# Encoder_y_alarmas.net
KiCad netlist of a schematic drawn in EAGLE
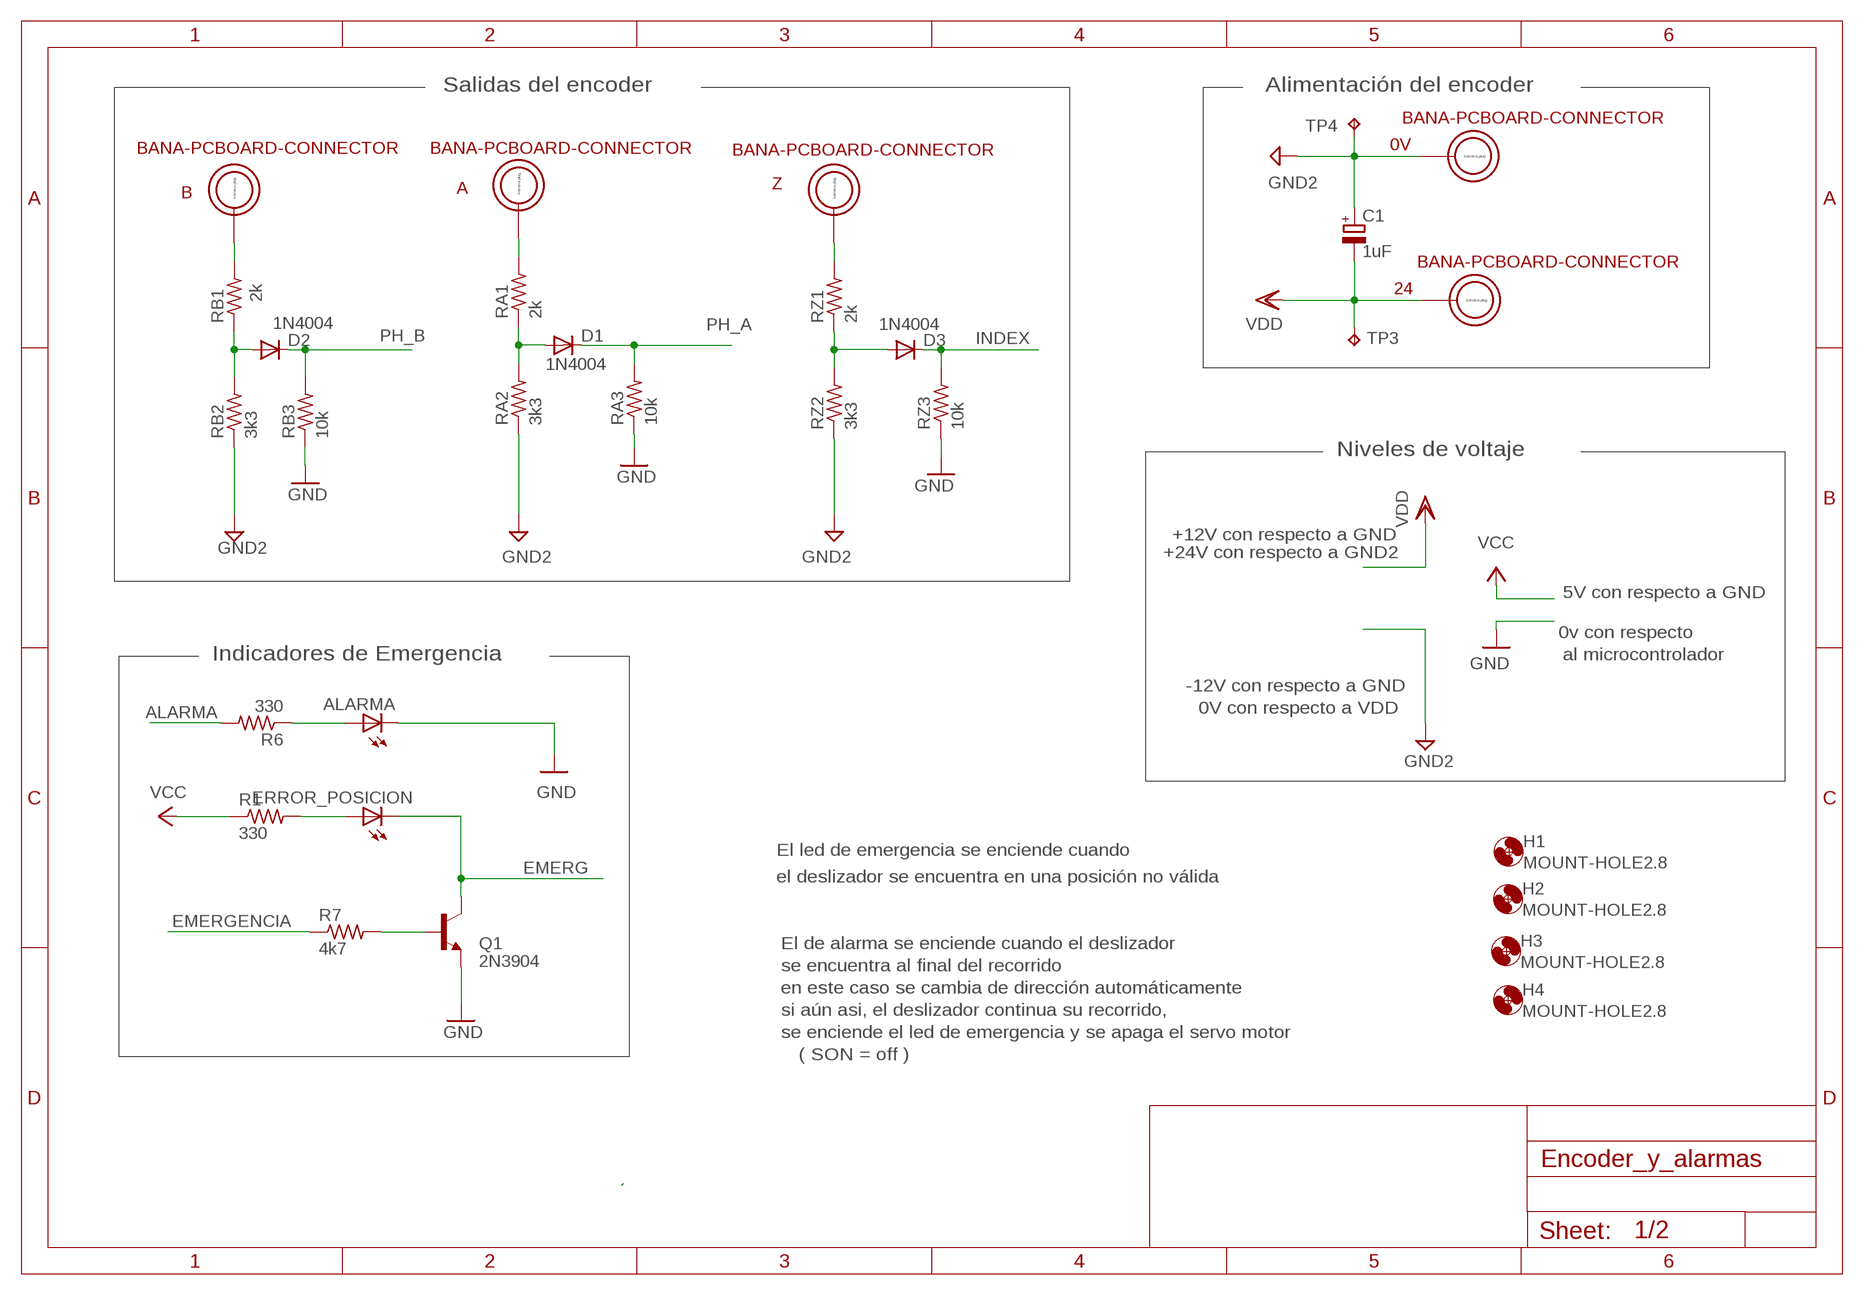
[diagram p0: schematic, sheet 1]
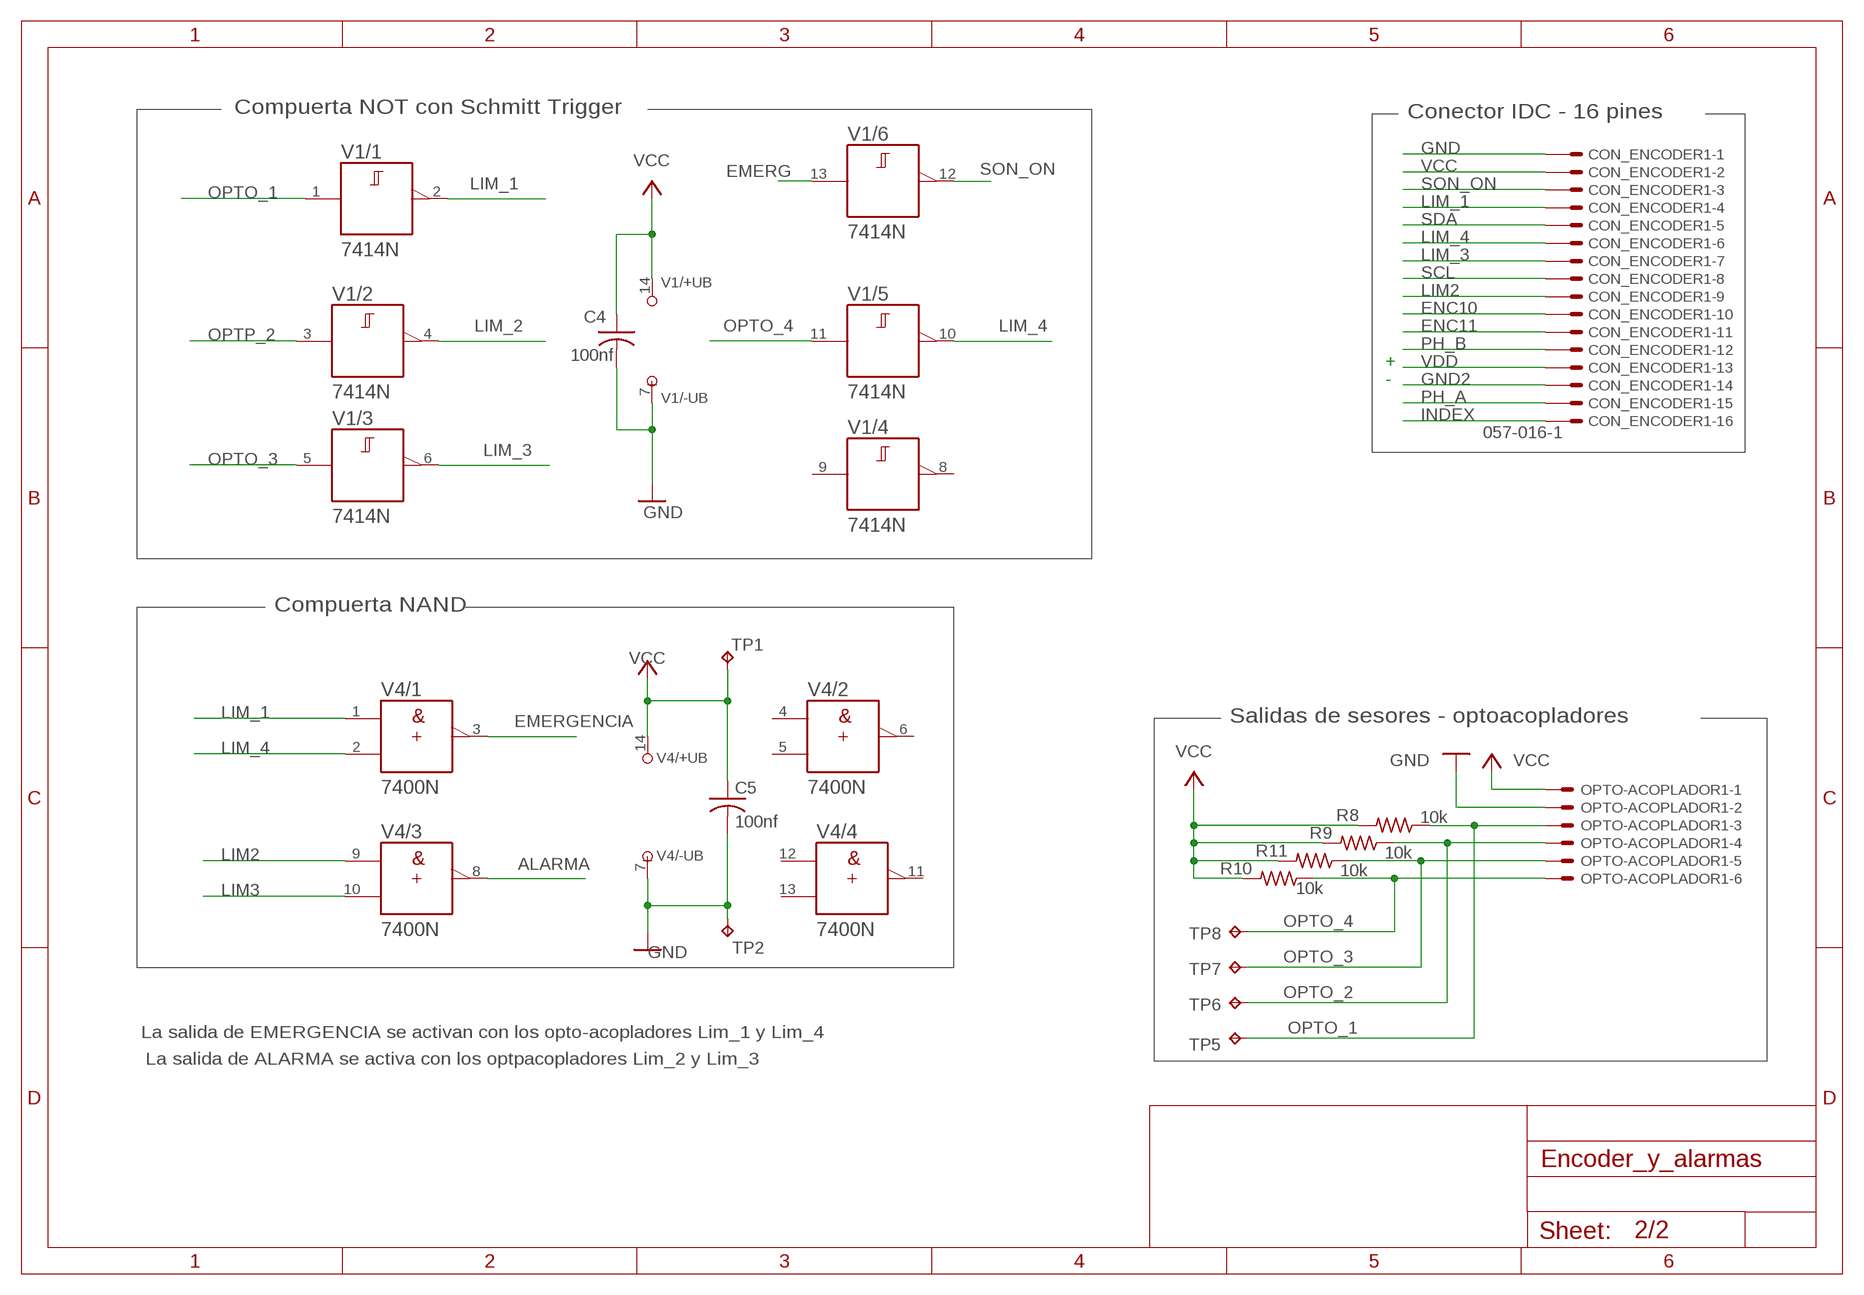
[diagram p1: schematic, sheet 2]

(export (version "E")
  (design (tool "Eeschema 10.0.6"))
  (components
    (comp (ref "C4")
      (value "100nf")
      (footprint "eagle-import:C025-024X044")
      (libsource (lib "eagle-import") (part "C-US025-024X044"))
    )
    (comp (ref "C5")
      (value "100nf")
      (footprint "eagle-import:C025-024X044")
      (libsource (lib "eagle-import") (part "C-US025-024X044"))
    )
    (comp (ref "CON_ENCODER1")
      (value "057-016-1")
      (footprint "eagle-import:057-016-1")
      (libsource (lib "eagle-import") (part "057-016-1"))
    )
    (comp (ref "OPTO-ACOPLADOR1")
      (value "22-23-2061")
      (footprint "eagle-import:22-23-2061")
      (fields (field (name "MF") "MOLEX"))
      (libsource (lib "eagle-import") (part "22-23-2061"))
    )
    (comp (ref "R8")
      (value "10k")
      (footprint "eagle-import:0204_7")
      (libsource (lib "eagle-import") (part "R-US_0204/7"))
    )
    (comp (ref "R9")
      (value "10k")
      (footprint "eagle-import:0204_7")
      (libsource (lib "eagle-import") (part "R-US_0204/7"))
    )
    (comp (ref "R10")
      (value "10k")
      (footprint "eagle-import:0204_7")
      (libsource (lib "eagle-import") (part "R-US_0204/7"))
    )
    (comp (ref "R11")
      (value "10k")
      (footprint "eagle-import:0204_7")
      (libsource (lib "eagle-import") (part "R-US_0204/7"))
    )
    (comp (ref "TP1")
      (value "TPB2,54")
      (footprint "eagle-import:B2,54")
      (libsource (lib "eagle-import") (part "TPB2,54"))
    )
    (comp (ref "TP2")
      (value "TPB2,54")
      (footprint "eagle-import:B2,54")
      (libsource (lib "eagle-import") (part "TPB2,54"))
    )
    (comp (ref "TP5")
      (value "TPB2,54")
      (footprint "eagle-import:B2,54")
      (libsource (lib "eagle-import") (part "TPB2,54"))
    )
    (comp (ref "TP6")
      (value "TPB2,54")
      (footprint "eagle-import:B2,54")
      (libsource (lib "eagle-import") (part "TPB2,54"))
    )
    (comp (ref "TP7")
      (value "TPB2,54")
      (footprint "eagle-import:B2,54")
      (libsource (lib "eagle-import") (part "TPB2,54"))
    )
    (comp (ref "TP8")
      (value "TPB2,54")
      (footprint "eagle-import:B2,54")
      (libsource (lib "eagle-import") (part "TPB2,54"))
    )
    (comp (ref "V1")
      (value "7414N")
      (footprint "eagle-import:DIL14")
      (libsource (lib "eagle-import") (part "7414N"))
    )
    (comp (ref "V4")
      (value "7400N")
      (footprint "eagle-import:DIL14")
      (libsource (lib "eagle-import") (part "7400N"))
    )
    (comp (ref "0V")
      (value "BANA-PCBOARD-CONNECTOR")
      (footprint "eagle-import:BANA_PLUG")
      (libsource (lib "eagle-import") (part "BANA-PCBOARD-CONNECTOR"))
    )
    (comp (ref "24")
      (value "BANA-PCBOARD-CONNECTOR")
      (footprint "eagle-import:BANA_PLUG")
      (libsource (lib "eagle-import") (part "BANA-PCBOARD-CONNECTOR"))
    )
    (comp (ref "A")
      (value "BANA-PCBOARD-CONNECTOR")
      (footprint "eagle-import:BANA_PLUG")
      (libsource (lib "eagle-import") (part "BANA-PCBOARD-CONNECTOR"))
    )
    (comp (ref "ALARMA")
      (value "LED5MM")
      (footprint "eagle-import:LED5MM")
      (libsource (lib "eagle-import") (part "LED5MM"))
    )
    (comp (ref "B")
      (value "BANA-PCBOARD-CONNECTOR")
      (footprint "eagle-import:BANA_PLUG")
      (libsource (lib "eagle-import") (part "BANA-PCBOARD-CONNECTOR"))
    )
    (comp (ref "C1")
      (value "1uF")
      (footprint "eagle-import:E2,5-6")
      (libsource (lib "eagle-import") (part "CPOL-EUE2.5-6"))
    )
    (comp (ref "D1")
      (value "1N4004")
      (footprint "eagle-import:DO41-10")
      (libsource (lib "eagle-import") (part "1N4004"))
    )
    (comp (ref "D2")
      (value "1N4004")
      (footprint "eagle-import:DO41-10")
      (libsource (lib "eagle-import") (part "1N4004"))
    )
    (comp (ref "D3")
      (value "1N4004")
      (footprint "eagle-import:DO41-10")
      (libsource (lib "eagle-import") (part "1N4004"))
    )
    (comp (ref "ERROR_POSICION")
      (value "LED5MM")
      (footprint "eagle-import:LED5MM")
      (libsource (lib "eagle-import") (part "LED5MM"))
    )
    (comp (ref "H1")
      (value "MOUNT-HOLE2.8")
      (footprint "eagle-import:2,8")
      (libsource (lib "eagle-import") (part "MOUNT-HOLE2.8"))
    )
    (comp (ref "H2")
      (value "MOUNT-HOLE2.8")
      (footprint "eagle-import:2,8")
      (libsource (lib "eagle-import") (part "MOUNT-HOLE2.8"))
    )
    (comp (ref "H3")
      (value "MOUNT-HOLE2.8")
      (footprint "eagle-import:2,8")
      (libsource (lib "eagle-import") (part "MOUNT-HOLE2.8"))
    )
    (comp (ref "H4")
      (value "MOUNT-HOLE2.8")
      (footprint "eagle-import:2,8")
      (libsource (lib "eagle-import") (part "MOUNT-HOLE2.8"))
    )
    (comp (ref "Q1")
      (value "2N3904")
      (footprint "eagle-import:TO92")
      (libsource (lib "eagle-import") (part "2N3904"))
    )
    (comp (ref "R1")
      (value "330")
      (footprint "eagle-import:0204_7")
      (libsource (lib "eagle-import") (part "R-US_0204/7"))
    )
    (comp (ref "R6")
      (value "330")
      (footprint "eagle-import:0204_7")
      (libsource (lib "eagle-import") (part "R-US_0204/7"))
    )
    (comp (ref "R7")
      (value "4k7")
      (footprint "eagle-import:0204_7")
      (libsource (lib "eagle-import") (part "R-US_0204/7"))
    )
    (comp (ref "RA1")
      (value "2k")
      (footprint "eagle-import:0204_7")
      (libsource (lib "eagle-import") (part "R-US_0204/7"))
    )
    (comp (ref "RA2")
      (value "3k3")
      (footprint "eagle-import:0204_7")
      (libsource (lib "eagle-import") (part "R-US_0204/7"))
    )
    (comp (ref "RA3")
      (value "10k")
      (footprint "eagle-import:0204_7")
      (libsource (lib "eagle-import") (part "R-US_0204/7"))
    )
    (comp (ref "RB1")
      (value "2k")
      (footprint "eagle-import:0204_7")
      (libsource (lib "eagle-import") (part "R-US_0204/7"))
    )
    (comp (ref "RB2")
      (value "3k3")
      (footprint "eagle-import:0204_7")
      (libsource (lib "eagle-import") (part "R-US_0204/7"))
    )
    (comp (ref "RB3")
      (value "10k")
      (footprint "eagle-import:0204_7")
      (libsource (lib "eagle-import") (part "R-US_0204/7"))
    )
    (comp (ref "RZ1")
      (value "2k")
      (footprint "eagle-import:0204_7")
      (libsource (lib "eagle-import") (part "R-US_0204/7"))
    )
    (comp (ref "RZ2")
      (value "3k3")
      (footprint "eagle-import:0204_7")
      (libsource (lib "eagle-import") (part "R-US_0204/7"))
    )
    (comp (ref "RZ3")
      (value "10k")
      (footprint "eagle-import:0204_7")
      (libsource (lib "eagle-import") (part "R-US_0204/7"))
    )
    (comp (ref "TP3")
      (value "TPB2,54")
      (footprint "eagle-import:B2,54")
      (libsource (lib "eagle-import") (part "TPB2,54"))
    )
    (comp (ref "TP4")
      (value "TPB2,54")
      (footprint "eagle-import:B2,54")
      (libsource (lib "eagle-import") (part "TPB2,54"))
    )
    (comp (ref "Z")
      (value "BANA-PCBOARD-CONNECTOR")
      (footprint "eagle-import:BANA_PLUG")
      (libsource (lib "eagle-import") (part "BANA-PCBOARD-CONNECTOR"))
    )
  )
  (nets
    (net (code "1") (name "ALARMA") (class "Default")
      (node (ref "R6") (pin "2") (pinfunction "2_2") (pintype "passive"))
      (node (ref "V4") (pin "8") (pinfunction "Y_8") (pintype "output"))
    )
    (net (code "2") (name "EMERG") (class "Default")
      (node (ref "ERROR_POSICION") (pin "K") (pinfunction "C_K") (pintype "passive"))
      (node (ref "Q1") (pin "1") (pinfunction "C_1") (pintype "passive"))
      (node (ref "V1") (pin "13") (pinfunction "A_13") (pintype "input"))
    )
    (net (code "3") (name "EMERGENCIA") (class "Default")
      (node (ref "R7") (pin "1") (pinfunction "1_1") (pintype "passive"))
      (node (ref "V4") (pin "3") (pinfunction "Y_3") (pintype "output"))
    )
    (net (code "4") (name "ENC10") (class "Default")
      (node (ref "CON_ENCODER1") (pin "10") (pinfunction "S_10") (pintype "passive"))
    )
    (net (code "5") (name "ENC11") (class "Default")
      (node (ref "CON_ENCODER1") (pin "11") (pinfunction "S_11") (pintype "passive"))
    )
    (net (code "6") (name "GND") (class "Default")
      (node (ref "ALARMA") (pin "K") (pinfunction "C_K") (pintype "passive"))
      (node (ref "C4") (pin "2") (pinfunction "2_2") (pintype "passive"))
      (node (ref "C5") (pin "2") (pinfunction "2_2") (pintype "passive"))
      (node (ref "CON_ENCODER1") (pin "1") (pinfunction "S_1") (pintype "passive"))
      (node (ref "OPTO-ACOPLADOR1") (pin "2") (pinfunction "S_2") (pintype "passive"))
      (node (ref "Q1") (pin "3") (pinfunction "E_3") (pintype "passive"))
      (node (ref "RA3") (pin "1") (pinfunction "1_1") (pintype "passive"))
      (node (ref "RB3") (pin "1") (pinfunction "1_1") (pintype "passive"))
      (node (ref "RZ3") (pin "1") (pinfunction "1_1") (pintype "passive"))
      (node (ref "TP2") (pin "TP") (pinfunction "TP_TP") (pintype "input"))
      (node (ref "V1") (pin "7") (pinfunction "-UB_7") (pintype "power_in"))
      (node (ref "V4") (pin "7") (pinfunction "-UB_7") (pintype "power_in"))
    )
    (net (code "7") (name "GND2") (class "Default")
      (node (ref "0V") (pin "P$1") (pinfunction "P$1_P$1") (pintype "bidirectional"))
      (node (ref "C1") (pin "+") (pinfunction "+_+") (pintype "passive"))
      (node (ref "CON_ENCODER1") (pin "14") (pinfunction "S_14") (pintype "passive"))
      (node (ref "RA2") (pin "1") (pinfunction "1_1") (pintype "passive"))
      (node (ref "RB2") (pin "1") (pinfunction "1_1") (pintype "passive"))
      (node (ref "RZ2") (pin "1") (pinfunction "1_1") (pintype "passive"))
      (node (ref "TP4") (pin "TP") (pinfunction "TP_TP") (pintype "input"))
    )
    (net (code "8") (name "INDEX") (class "Default")
      (node (ref "CON_ENCODER1") (pin "16") (pinfunction "S_16") (pintype "passive"))
      (node (ref "D3") (pin "C") (pinfunction "C_C") (pintype "passive"))
      (node (ref "RZ3") (pin "2") (pinfunction "2_2") (pintype "passive"))
    )
    (net (code "9") (name "LIM2") (class "Default")
      (node (ref "CON_ENCODER1") (pin "9") (pinfunction "S_9") (pintype "passive"))
      (node (ref "V4") (pin "9") (pinfunction "A_9") (pintype "input"))
    )
    (net (code "10") (name "LIM3") (class "Default")
      (node (ref "V4") (pin "10") (pinfunction "B_10") (pintype "input"))
    )
    (net (code "11") (name "LIM_1") (class "Default")
      (node (ref "CON_ENCODER1") (pin "4") (pinfunction "S_4") (pintype "passive"))
      (node (ref "V1") (pin "2") (pinfunction "Y_2") (pintype "output"))
      (node (ref "V4") (pin "1") (pinfunction "A_1") (pintype "input"))
    )
    (net (code "12") (name "LIM_2") (class "Default")
      (node (ref "V1") (pin "4") (pinfunction "Y_4") (pintype "output"))
    )
    (net (code "13") (name "LIM_3") (class "Default")
      (node (ref "CON_ENCODER1") (pin "7") (pinfunction "S_7") (pintype "passive"))
      (node (ref "V1") (pin "6") (pinfunction "Y_6") (pintype "output"))
    )
    (net (code "14") (name "LIM_4") (class "Default")
      (node (ref "CON_ENCODER1") (pin "6") (pinfunction "S_6") (pintype "passive"))
      (node (ref "V1") (pin "10") (pinfunction "Y_10") (pintype "output"))
      (node (ref "V4") (pin "2") (pinfunction "B_2") (pintype "input"))
    )
    (net (code "15") (name "Net-(A-PadP$1)") (class "Default")
      (node (ref "A") (pin "P$1") (pinfunction "P$1_P$1") (pintype "bidirectional"))
      (node (ref "RA1") (pin "2") (pinfunction "2_2") (pintype "passive"))
    )
    (net (code "16") (name "Net-(ALARMA-PadA)") (class "Default")
      (node (ref "ALARMA") (pin "A") (pinfunction "A_A") (pintype "passive"))
      (node (ref "R6") (pin "1") (pinfunction "1_1") (pintype "passive"))
    )
    (net (code "17") (name "Net-(B-PadP$1)") (class "Default")
      (node (ref "B") (pin "P$1") (pinfunction "P$1_P$1") (pintype "bidirectional"))
      (node (ref "RB1") (pin "2") (pinfunction "2_2") (pintype "passive"))
    )
    (net (code "18") (name "Net-(D1-PadA)") (class "Default")
      (node (ref "D1") (pin "A") (pinfunction "A_A") (pintype "passive"))
      (node (ref "RA1") (pin "1") (pinfunction "1_1") (pintype "passive"))
      (node (ref "RA2") (pin "2") (pinfunction "2_2") (pintype "passive"))
    )
    (net (code "19") (name "Net-(D2-PadA)") (class "Default")
      (node (ref "D2") (pin "A") (pinfunction "A_A") (pintype "passive"))
      (node (ref "RB1") (pin "1") (pinfunction "1_1") (pintype "passive"))
      (node (ref "RB2") (pin "2") (pinfunction "2_2") (pintype "passive"))
    )
    (net (code "20") (name "Net-(D3-PadA)") (class "Default")
      (node (ref "D3") (pin "A") (pinfunction "A_A") (pintype "passive"))
      (node (ref "RZ1") (pin "1") (pinfunction "1_1") (pintype "passive"))
      (node (ref "RZ2") (pin "2") (pinfunction "2_2") (pintype "passive"))
    )
    (net (code "21") (name "Net-(ERROR_POSICION-PadA)") (class "Default")
      (node (ref "ERROR_POSICION") (pin "A") (pinfunction "A_A") (pintype "passive"))
      (node (ref "R1") (pin "2") (pinfunction "2_2") (pintype "passive"))
    )
    (net (code "22") (name "Net-(Q1-B)") (class "Default")
      (node (ref "Q1") (pin "2") (pinfunction "B_2") (pintype "passive"))
      (node (ref "R7") (pin "2") (pinfunction "2_2") (pintype "passive"))
    )
    (net (code "23") (name "Net-(RZ1-Pad2)") (class "Default")
      (node (ref "RZ1") (pin "2") (pinfunction "2_2") (pintype "passive"))
      (node (ref "Z") (pin "P$1") (pinfunction "P$1_P$1") (pintype "bidirectional"))
    )
    (net (code "24") (name "OPTO_1") (class "Default")
      (node (ref "OPTO-ACOPLADOR1") (pin "3") (pinfunction "S_3") (pintype "passive"))
      (node (ref "R8") (pin "1") (pinfunction "1_1") (pintype "passive"))
      (node (ref "TP5") (pin "TP") (pinfunction "TP_TP") (pintype "input"))
      (node (ref "V1") (pin "1") (pinfunction "A_1") (pintype "input"))
    )
    (net (code "25") (name "OPTO_2") (class "Default")
      (node (ref "OPTO-ACOPLADOR1") (pin "4") (pinfunction "S_4") (pintype "passive"))
      (node (ref "R9") (pin "1") (pinfunction "1_1") (pintype "passive"))
      (node (ref "TP6") (pin "TP") (pinfunction "TP_TP") (pintype "input"))
    )
    (net (code "26") (name "OPTO_3") (class "Default")
      (node (ref "OPTO-ACOPLADOR1") (pin "5") (pinfunction "S_5") (pintype "passive"))
      (node (ref "R11") (pin "1") (pinfunction "1_1") (pintype "passive"))
      (node (ref "TP7") (pin "TP") (pinfunction "TP_TP") (pintype "input"))
      (node (ref "V1") (pin "5") (pinfunction "A_5") (pintype "input"))
    )
    (net (code "27") (name "OPTO_4") (class "Default")
      (node (ref "OPTO-ACOPLADOR1") (pin "6") (pinfunction "S_6") (pintype "passive"))
      (node (ref "R10") (pin "1") (pinfunction "1_1") (pintype "passive"))
      (node (ref "TP8") (pin "TP") (pinfunction "TP_TP") (pintype "input"))
      (node (ref "V1") (pin "11") (pinfunction "A_11") (pintype "input"))
    )
    (net (code "28") (name "OPTP_2") (class "Default")
      (node (ref "V1") (pin "3") (pinfunction "A_3") (pintype "input"))
    )
    (net (code "29") (name "PH_A") (class "Default")
      (node (ref "CON_ENCODER1") (pin "15") (pinfunction "S_15") (pintype "passive"))
      (node (ref "D1") (pin "C") (pinfunction "C_C") (pintype "passive"))
      (node (ref "RA3") (pin "2") (pinfunction "2_2") (pintype "passive"))
    )
    (net (code "30") (name "PH_B") (class "Default")
      (node (ref "CON_ENCODER1") (pin "12") (pinfunction "S_12") (pintype "passive"))
      (node (ref "D2") (pin "C") (pinfunction "C_C") (pintype "passive"))
      (node (ref "RB3") (pin "2") (pinfunction "2_2") (pintype "passive"))
    )
    (net (code "31") (name "SCL") (class "Default")
      (node (ref "CON_ENCODER1") (pin "8") (pinfunction "S_8") (pintype "passive"))
    )
    (net (code "32") (name "SDA") (class "Default")
      (node (ref "CON_ENCODER1") (pin "5") (pinfunction "S_5") (pintype "passive"))
    )
    (net (code "33") (name "SON_ON") (class "Default")
      (node (ref "CON_ENCODER1") (pin "3") (pinfunction "S_3") (pintype "passive"))
      (node (ref "V1") (pin "12") (pinfunction "Y_12") (pintype "output"))
    )
    (net (code "34") (name "VCC") (class "Default")
      (node (ref "C4") (pin "1") (pinfunction "1_1") (pintype "passive"))
      (node (ref "C5") (pin "1") (pinfunction "1_1") (pintype "passive"))
      (node (ref "CON_ENCODER1") (pin "2") (pinfunction "S_2") (pintype "passive"))
      (node (ref "OPTO-ACOPLADOR1") (pin "1") (pinfunction "S_1") (pintype "passive"))
      (node (ref "R1") (pin "1") (pinfunction "1_1") (pintype "passive"))
      (node (ref "R10") (pin "2") (pinfunction "2_2") (pintype "passive"))
      (node (ref "R11") (pin "2") (pinfunction "2_2") (pintype "passive"))
      (node (ref "R8") (pin "2") (pinfunction "2_2") (pintype "passive"))
      (node (ref "R9") (pin "2") (pinfunction "2_2") (pintype "passive"))
      (node (ref "TP1") (pin "TP") (pinfunction "TP_TP") (pintype "input"))
      (node (ref "V1") (pin "14") (pinfunction "+UB_14") (pintype "power_in"))
      (node (ref "V4") (pin "14") (pinfunction "+UB_14") (pintype "power_in"))
    )
    (net (code "35") (name "VDD") (class "Default")
      (node (ref "24") (pin "P$1") (pinfunction "P$1_P$1") (pintype "bidirectional"))
      (node (ref "C1") (pin "-") (pinfunction "-_-") (pintype "passive"))
      (node (ref "CON_ENCODER1") (pin "13") (pinfunction "S_13") (pintype "passive"))
      (node (ref "TP3") (pin "TP") (pinfunction "TP_TP") (pintype "input"))
    )
    (net (code "36") (name "unconnected-(V1F-A-Pad9)") (class "Default")
      (node (ref "V1") (pin "9") (pinfunction "A_9") (pintype "input"))
    )
    (net (code "37") (name "unconnected-(V1F-Y-Pad8)") (class "Default")
      (node (ref "V1") (pin "8") (pinfunction "Y_8") (pintype "output"))
    )
    (net (code "38") (name "unconnected-(V4D-A-Pad4)") (class "Default")
      (node (ref "V4") (pin "4") (pinfunction "A_4") (pintype "input"))
    )
    (net (code "39") (name "unconnected-(V4D-B-Pad5)") (class "Default")
      (node (ref "V4") (pin "5") (pinfunction "B_5") (pintype "input"))
    )
    (net (code "40") (name "unconnected-(V4D-Y-Pad6)") (class "Default")
      (node (ref "V4") (pin "6") (pinfunction "Y_6") (pintype "output"))
    )
    (net (code "41") (name "unconnected-(V4F-A-Pad12)") (class "Default")
      (node (ref "V4") (pin "12") (pinfunction "A_12") (pintype "input"))
    )
    (net (code "42") (name "unconnected-(V4F-B-Pad13)") (class "Default")
      (node (ref "V4") (pin "13") (pinfunction "B_13") (pintype "input"))
    )
    (net (code "43") (name "unconnected-(V4F-Y-Pad11)") (class "Default")
      (node (ref "V4") (pin "11") (pinfunction "Y_11") (pintype "output"))
    )
  )
)
